# Powerboard_in_ROV_V1_0.net
KiCad netlist of a schematic drawn in Altium Designer
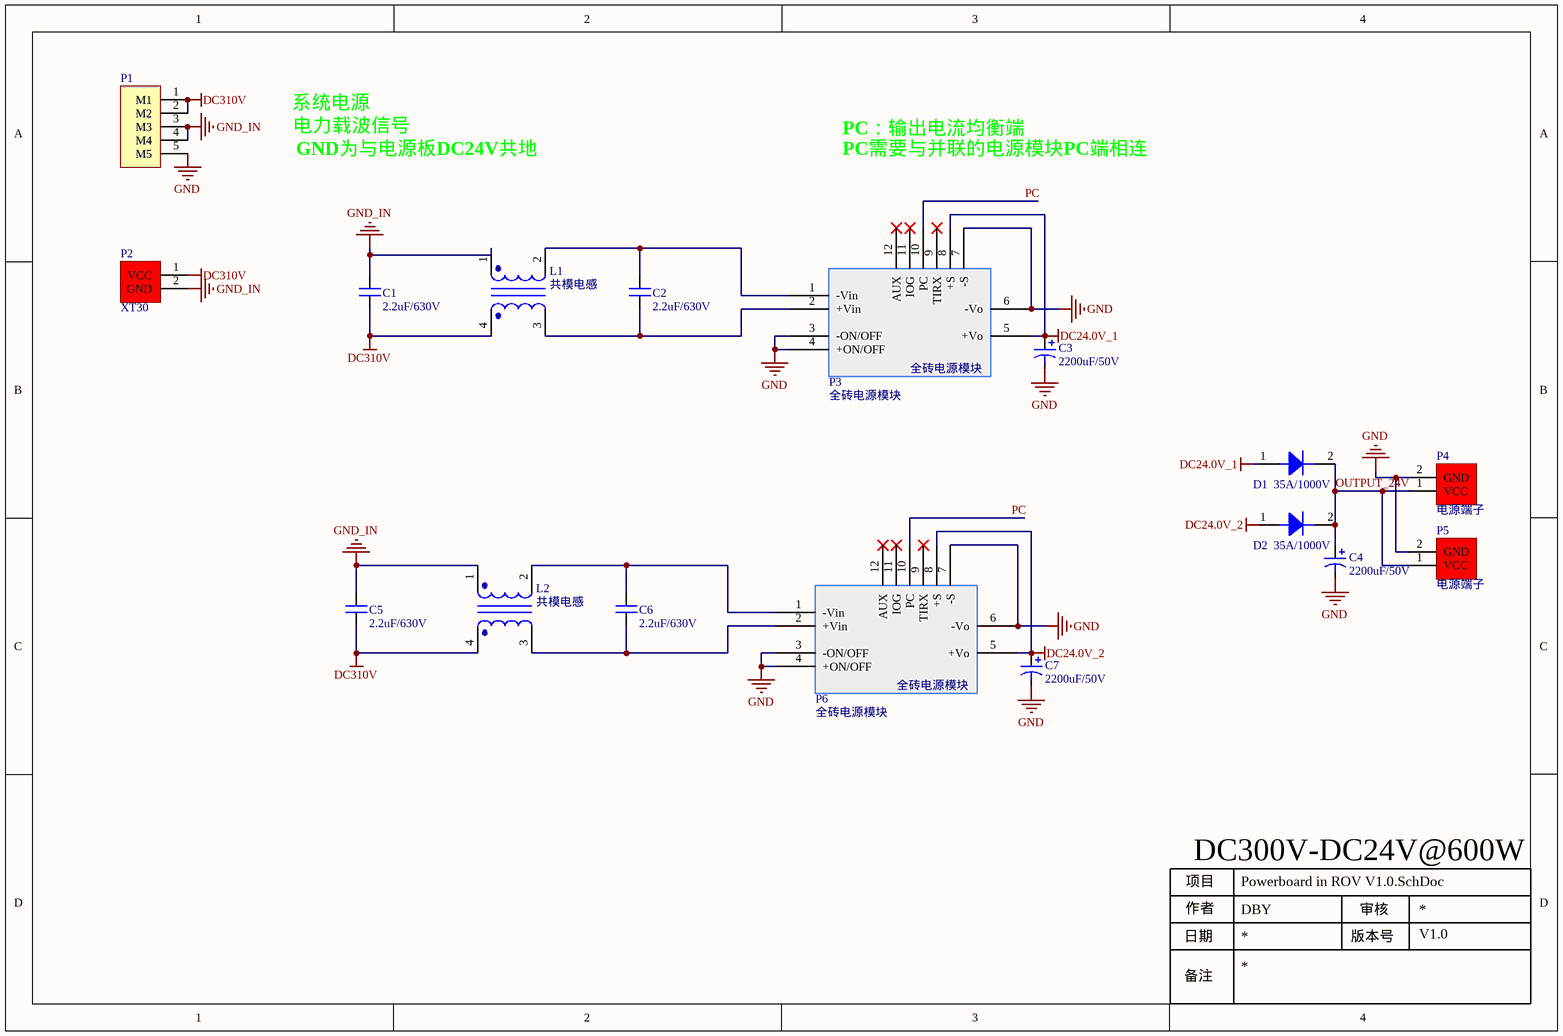
[diagram p0: Powerboard in ROV V1.0.SchDoc]

(export (version "E")
  (design (tool "Eeschema 10.0.6"))
  (components
    (comp (ref "C1")
      (value "2.2uF/630V")
      (footprint "CCB 电容(27mm)")
      (description "无极性CCB电容")
      (libsource (lib "集大电协1.5") (part "Cap2"))
    )
    (comp (ref "C2")
      (value "2.2uF/630V")
      (footprint "CCB 电容(27mm)")
      (description "无极性CCB电容")
      (libsource (lib "集大电协1.5") (part "Cap2"))
    )
    (comp (ref "C3")
      (value "2200uF/50V")
      (footprint "CAP 7.5*16*31.5-H - GD")
      (description "直插极性电容")
      (libsource (lib "集大电协1.5") (part "Cap3"))
    )
    (comp (ref "C4")
      (value "2200uF/50V")
      (footprint "CAP 7.5*16*31.5-H - GD")
      (description "直插极性电容")
      (libsource (lib "集大电协1.5") (part "Cap3"))
    )
    (comp (ref "C5")
      (value "2.2uF/630V")
      (footprint "CCB 电容(27mm)")
      (description "无极性CCB电容")
      (libsource (lib "集大电协1.5") (part "Cap2"))
    )
    (comp (ref "C6")
      (value "2.2uF/630V")
      (footprint "CCB 电容(27mm)")
      (description "无极性CCB电容")
      (libsource (lib "集大电协1.5") (part "Cap2"))
    )
    (comp (ref "C7")
      (value "2200uF/50V")
      (footprint "CAP 7.5*16*31.5-H - GD")
      (description "直插极性电容")
      (libsource (lib "集大电协1.5") (part "Cap3"))
    )
    (comp (ref "D1")
      (value "35A/1000V")
      (footprint "R-6")
      (description "二极管")
      (libsource (lib "集大电协1.5") (part "Diode"))
    )
    (comp (ref "D2")
      (value "35A/1000V")
      (footprint "R-6")
      (description "二极管")
      (libsource (lib "集大电协1.5") (part "Diode"))
    )
    (comp (ref "L1") (value "共模电感") (footprint "UU10.5") (libsource (lib "集大电协1.5") (part "共模电感")))
    (comp (ref "L2") (value "共模电感") (footprint "UU10.5") (libsource (lib "集大电协1.5") (part "共模电感")))
    (comp (ref "P1")
      (value "~")
      (footprint "PH2.0-WS-5P")
      (description "接线端子-5PIN")
      (libsource (lib "集大电协1.5") (part "接线端子-5PIN"))
    )
    (comp (ref "P2") (value "XT30") (footprint "XT30PW-M") (libsource (lib "") (part "电源端子_1")))
    (comp (ref "P3") (value "全砖电源模块") (footprint "全砖电源模块") (libsource (lib "集大电协1.5") (part "全砖电源模块（迪龙）")))
    (comp (ref "P4") (value "电源端子") (footprint "XT60PW-F") (libsource (lib "集大电协1.5") (part "电源端子")))
    (comp (ref "P5") (value "电源端子") (footprint "XT60PW-F") (libsource (lib "集大电协1.5") (part "电源端子")))
    (comp (ref "P6") (value "全砖电源模块") (footprint "全砖电源模块") (libsource (lib "集大电协1.5") (part "全砖电源模块（迪龙）")))
  )
  (nets
    (net (code "1") (name "/OUTPUT_24V") (class "Default")
      (node (ref "C4") (pin "1") (pinfunction "1_1") (pintype "passive"))
      (node (ref "D1") (pin "2") (pinfunction "2_2") (pintype "passive"))
      (node (ref "D2") (pin "2") (pinfunction "2_2") (pintype "passive"))
      (node (ref "P4") (pin "1") (pinfunction "VCC_1") (pintype "passive"))
      (node (ref "P5") (pin "1") (pinfunction "VCC_1") (pintype "passive"))
    )
    (net (code "2") (name "/PC") (class "Default")
      (node (ref "P3") (pin "10") (pinfunction "PC_10") (pintype "passive"))
      (node (ref "P6") (pin "10") (pinfunction "PC_10") (pintype "passive"))
    )
    (net (code "3") (name "DC24.0V_1") (class "Default")
      (node (ref "C3") (pin "1") (pinfunction "1_1") (pintype "passive"))
      (node (ref "D1") (pin "1") (pintype "passive"))
      (node (ref "P3") (pin "5") (pinfunction "+Vo_5") (pintype "passive"))
      (node (ref "P3") (pin "8") (pinfunction "+S_8") (pintype "passive"))
    )
    (net (code "4") (name "DC24.0V_2") (class "Default")
      (node (ref "C7") (pin "1") (pinfunction "1_1") (pintype "passive"))
      (node (ref "D2") (pin "1") (pintype "passive"))
      (node (ref "P6") (pin "5") (pinfunction "+Vo_5") (pintype "passive"))
      (node (ref "P6") (pin "8") (pinfunction "+S_8") (pintype "passive"))
    )
    (net (code "5") (name "DC310V") (class "Default")
      (node (ref "C1") (pin "2") (pinfunction "2_2") (pintype "passive"))
      (node (ref "C5") (pin "1") (pinfunction "1_1") (pintype "passive"))
      (node (ref "L1") (pin "4") (pinfunction "4_4") (pintype "passive"))
      (node (ref "L2") (pin "4") (pinfunction "4_4") (pintype "passive"))
      (node (ref "P1") (pin "1") (pinfunction "M1_1") (pintype "passive"))
      (node (ref "P1") (pin "2") (pinfunction "M2_2") (pintype "passive"))
      (node (ref "P2") (pin "1") (pinfunction "VCC_1") (pintype "passive"))
    )
    (net (code "6") (name "GND") (class "Default")
      (node (ref "C3") (pin "2") (pinfunction "2_2") (pintype "passive"))
      (node (ref "C4") (pin "2") (pinfunction "2_2") (pintype "passive"))
      (node (ref "C7") (pin "2") (pinfunction "2_2") (pintype "passive"))
      (node (ref "P1") (pin "5") (pinfunction "M5_5") (pintype "passive"))
      (node (ref "P3") (pin "3") (pinfunction "-ON/OFF_3") (pintype "passive"))
      (node (ref "P3") (pin "4") (pinfunction "+ON/OFF_4") (pintype "passive"))
      (node (ref "P3") (pin "6") (pinfunction "-Vo_6") (pintype "passive"))
      (node (ref "P3") (pin "7") (pinfunction "-S_7") (pintype "passive"))
      (node (ref "P4") (pin "2") (pinfunction "GND_2") (pintype "passive"))
      (node (ref "P5") (pin "2") (pinfunction "GND_2") (pintype "passive"))
      (node (ref "P6") (pin "3") (pinfunction "-ON/OFF_3") (pintype "passive"))
      (node (ref "P6") (pin "4") (pinfunction "+ON/OFF_4") (pintype "passive"))
      (node (ref "P6") (pin "6") (pinfunction "-Vo_6") (pintype "passive"))
      (node (ref "P6") (pin "7") (pinfunction "-S_7") (pintype "passive"))
    )
    (net (code "7") (name "GND_IN") (class "Default")
      (node (ref "C1") (pin "1") (pinfunction "1_1") (pintype "passive"))
      (node (ref "C5") (pin "2") (pinfunction "2_2") (pintype "passive"))
      (node (ref "L1") (pin "1") (pinfunction "1_1") (pintype "passive"))
      (node (ref "L2") (pin "1") (pinfunction "1_1") (pintype "passive"))
      (node (ref "P1") (pin "3") (pinfunction "M3_3") (pintype "passive"))
      (node (ref "P1") (pin "4") (pinfunction "M4_4") (pintype "passive"))
      (node (ref "P2") (pin "2") (pinfunction "GND_2") (pintype "passive"))
    )
    (net (code "8") (name "Net-(P3-+Vin)") (class "Default")
      (node (ref "C2") (pin "1") (pinfunction "1_1") (pintype "passive"))
      (node (ref "L1") (pin "3") (pinfunction "3_3") (pintype "passive"))
      (node (ref "P3") (pin "2") (pinfunction "+Vin_2") (pintype "passive"))
    )
    (net (code "9") (name "Net-(P3--Vin)") (class "Default")
      (node (ref "C2") (pin "2") (pinfunction "2_2") (pintype "passive"))
      (node (ref "L1") (pin "2") (pinfunction "2_2") (pintype "passive"))
      (node (ref "P3") (pin "1") (pinfunction "-Vin_1") (pintype "passive"))
    )
    (net (code "10") (name "Net-(P6-+Vin)") (class "Default")
      (node (ref "C6") (pin "1") (pinfunction "1_1") (pintype "passive"))
      (node (ref "L2") (pin "3") (pinfunction "3_3") (pintype "passive"))
      (node (ref "P6") (pin "2") (pinfunction "+Vin_2") (pintype "passive"))
    )
    (net (code "11") (name "Net-(P6--Vin)") (class "Default")
      (node (ref "C6") (pin "2") (pinfunction "2_2") (pintype "passive"))
      (node (ref "L2") (pin "2") (pinfunction "2_2") (pintype "passive"))
      (node (ref "P6") (pin "1") (pinfunction "-Vin_1") (pintype "passive"))
    )
    (net (code "12") (name "unconnected-(P3-AUX-Pad12)") (class "Default")
      (node (ref "P3") (pin "12") (pinfunction "AUX_12") (pintype "passive+no_connect"))
    )
    (net (code "13") (name "unconnected-(P3-IOG-Pad11)") (class "Default")
      (node (ref "P3") (pin "11") (pinfunction "IOG_11") (pintype "passive+no_connect"))
    )
    (net (code "14") (name "unconnected-(P3-TIRX-Pad9)") (class "Default")
      (node (ref "P3") (pin "9") (pinfunction "TIRX_9") (pintype "passive+no_connect"))
    )
    (net (code "15") (name "unconnected-(P6-AUX-Pad12)") (class "Default")
      (node (ref "P6") (pin "12") (pinfunction "AUX_12") (pintype "passive+no_connect"))
    )
    (net (code "16") (name "unconnected-(P6-IOG-Pad11)") (class "Default")
      (node (ref "P6") (pin "11") (pinfunction "IOG_11") (pintype "passive+no_connect"))
    )
    (net (code "17") (name "unconnected-(P6-TIRX-Pad9)") (class "Default")
      (node (ref "P6") (pin "9") (pinfunction "TIRX_9") (pintype "passive+no_connect"))
    )
  )
)
